# USBHUB-FE1_1S.net
KiCad netlist of a schematic drawn in Altium Designer
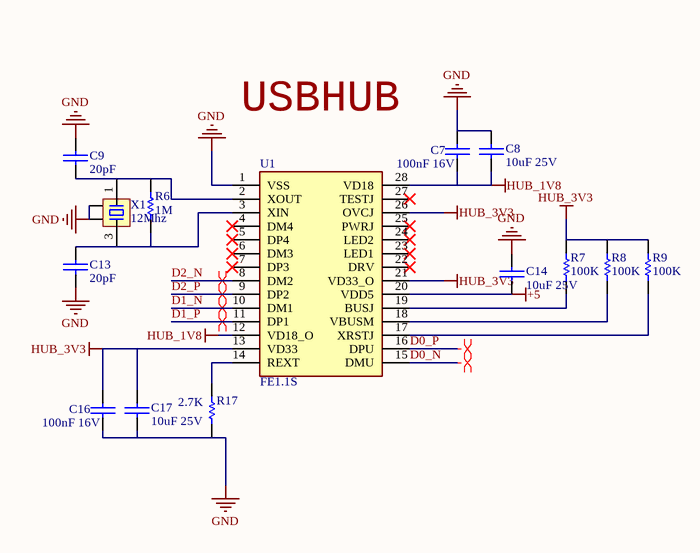
[diagram p0: USBHUB-FE1.1S.SchDoc]

(export (version "E")
  (design (tool "Eeschema 10.0.6"))
  (components
    (comp (ref "C7")
      (value "100nF 16V")
      (footprint "0402C")
      (description "CAP-NP")
      (libsource (lib "电容") (part "CAP-NP"))
    )
    (comp (ref "C8")
      (value "10uF 25V")
      (footprint "Capacitance:0805C")
      (description "CAP-NP")
      (libsource (lib "电容") (part "CAP-NP"))
    )
    (comp (ref "C9") (value "20pF") (footprint "0402C") (libsource (lib "电容") (part "CAP-NP")))
    (comp (ref "C13") (value "20pF") (footprint "0402C") (libsource (lib "电容") (part "CAP-NP")))
    (comp (ref "C14")
      (value "10uF 25V")
      (footprint "Capacitance:0805C")
      (description "CAP-NP")
      (libsource (lib "电容") (part "CAP-NP"))
    )
    (comp (ref "C16")
      (value "100nF 16V")
      (footprint "0402C")
      (description "CAP-NP")
      (libsource (lib "电容") (part "CAP-NP"))
    )
    (comp (ref "C17")
      (value "10uF 25V")
      (footprint "Capacitance:0805C")
      (description "CAP-NP")
      (libsource (lib "电容") (part "CAP-NP"))
    )
    (comp (ref "R6") (value "1M") (footprint "0402R") (libsource (lib "电阻") (part "RES")))
    (comp (ref "R7") (value "100K") (footprint "0402R") (libsource (lib "电阻") (part "RES")))
    (comp (ref "R8") (value "100K") (footprint "0402R") (libsource (lib "电阻") (part "RES")))
    (comp (ref "R9") (value "100K") (footprint "0402R") (libsource (lib "电阻") (part "RES")))
    (comp (ref "R17") (value "2.7K") (footprint "0402R") (libsource (lib "电阻") (part "RES")))
    (comp (ref "U1")
      (value "FE1.1S")
      (footprint "SamacSys:SOP64P600X175-28N")
      (description "Integrated Circuit")
      (libsource (lib "*") (part "FE1.1S"))
    )
    (comp (ref "X1")
      (value "12Mhz")
      (footprint "Crystals Oscillators:OSC 3225-4P")
      (description "XTAL-4P")
      (libsource (lib "晶振") (part "XTAL-4P"))
    )
  )
  (nets
    (net (code "1") (name "+5") (class "Default")
      (node (ref "C14") (pin "2") (pinfunction "2_2") (pintype "passive"))
      (node (ref "U1") (pin "20") (pinfunction "VDD5_20") (pintype "passive"))
    )
    (net (code "2") (name "/D0_N") (class "Default")
      (node (ref "U1") (pin "15") (pinfunction "DMU_15") (pintype "passive"))
    )
    (net (code "3") (name "/D0_P") (class "Default")
      (node (ref "U1") (pin "16") (pinfunction "DPU_16") (pintype "passive"))
    )
    (net (code "4") (name "/D1_N") (class "Default")
      (node (ref "U1") (pin "10") (pinfunction "DM1_10") (pintype "passive"))
    )
    (net (code "5") (name "/D1_P") (class "Default")
      (node (ref "U1") (pin "11") (pinfunction "DP1_11") (pintype "passive"))
    )
    (net (code "6") (name "/D2_N") (class "Default")
      (node (ref "U1") (pin "8") (pinfunction "DM2_8") (pintype "passive"))
    )
    (net (code "7") (name "/D2_P") (class "Default")
      (node (ref "U1") (pin "9") (pinfunction "DP2_9") (pintype "passive"))
    )
    (net (code "8") (name "GND") (class "Default")
      (node (ref "C13") (pin "1") (pinfunction "1_1") (pintype "passive"))
      (node (ref "C14") (pin "1") (pinfunction "1_1") (pintype "passive"))
      (node (ref "C16") (pin "1") (pinfunction "1_1") (pintype "passive"))
      (node (ref "C17") (pin "2") (pinfunction "2_2") (pintype "passive"))
      (node (ref "C7") (pin "2") (pinfunction "2_2") (pintype "passive"))
      (node (ref "C8") (pin "1") (pinfunction "1_1") (pintype "passive"))
      (node (ref "C9") (pin "2") (pinfunction "2_2") (pintype "passive"))
      (node (ref "R17") (pin "1") (pinfunction "1_1") (pintype "passive"))
      (node (ref "U1") (pin "1") (pinfunction "VSS_1") (pintype "passive"))
      (node (ref "X1") (pin "2") (pinfunction "2_2") (pintype "passive"))
      (node (ref "X1") (pin "4") (pinfunction "4_4") (pintype "passive"))
    )
    (net (code "9") (name "HUB_1V8") (class "Default")
      (node (ref "C7") (pin "1") (pinfunction "1_1") (pintype "passive"))
      (node (ref "C8") (pin "2") (pinfunction "2_2") (pintype "passive"))
      (node (ref "U1") (pin "12") (pinfunction "VD18_O_12") (pintype "passive"))
      (node (ref "U1") (pin "28") (pinfunction "VD18_28") (pintype "passive"))
    )
    (net (code "10") (name "HUB_3V3") (class "Default")
      (node (ref "C16") (pin "2") (pinfunction "2_2") (pintype "passive"))
      (node (ref "C17") (pin "1") (pinfunction "1_1") (pintype "passive"))
      (node (ref "R7") (pin "2") (pinfunction "2_2") (pintype "passive"))
      (node (ref "R8") (pin "2") (pinfunction "2_2") (pintype "passive"))
      (node (ref "R9") (pin "2") (pinfunction "2_2") (pintype "passive"))
      (node (ref "U1") (pin "13") (pinfunction "VD33_13") (pintype "passive"))
      (node (ref "U1") (pin "21") (pinfunction "VD33_O_21") (pintype "passive"))
      (node (ref "U1") (pin "26") (pinfunction "OVCJ_26") (pintype "passive"))
    )
    (net (code "11") (name "Net-(U1-BUSJ)") (class "Default")
      (node (ref "R7") (pin "1") (pinfunction "1_1") (pintype "passive"))
      (node (ref "U1") (pin "19") (pinfunction "BUSJ_19") (pintype "passive"))
    )
    (net (code "12") (name "Net-(U1-REXT)") (class "Default")
      (node (ref "R17") (pin "2") (pinfunction "2_2") (pintype "passive"))
      (node (ref "U1") (pin "14") (pinfunction "REXT_14") (pintype "passive"))
    )
    (net (code "13") (name "Net-(U1-VBUSM)") (class "Default")
      (node (ref "R8") (pin "1") (pinfunction "1_1") (pintype "passive"))
      (node (ref "U1") (pin "18") (pinfunction "VBUSM_18") (pintype "passive"))
    )
    (net (code "14") (name "Net-(U1-XIN)") (class "Default")
      (node (ref "C13") (pin "2") (pinfunction "2_2") (pintype "passive"))
      (node (ref "R6") (pin "1") (pinfunction "1_1") (pintype "passive"))
      (node (ref "U1") (pin "3") (pinfunction "XIN_3") (pintype "passive"))
      (node (ref "X1") (pin "3") (pinfunction "3_3") (pintype "passive"))
    )
    (net (code "15") (name "Net-(U1-XOUT)") (class "Default")
      (node (ref "C9") (pin "1") (pinfunction "1_1") (pintype "passive"))
      (node (ref "R6") (pin "2") (pinfunction "2_2") (pintype "passive"))
      (node (ref "U1") (pin "2") (pinfunction "XOUT_2") (pintype "passive"))
      (node (ref "X1") (pin "1") (pinfunction "1_1") (pintype "passive"))
    )
    (net (code "16") (name "Net-(U1-XRSTJ)") (class "Default")
      (node (ref "R9") (pin "1") (pinfunction "1_1") (pintype "passive"))
      (node (ref "U1") (pin "17") (pinfunction "XRSTJ_17") (pintype "passive"))
    )
    (net (code "17") (name "unconnected-(U1-DM3-Pad6)") (class "Default")
      (node (ref "U1") (pin "6") (pinfunction "DM3_6") (pintype "passive+no_connect"))
    )
    (net (code "18") (name "unconnected-(U1-DM4-Pad4)") (class "Default")
      (node (ref "U1") (pin "4") (pinfunction "DM4_4") (pintype "passive+no_connect"))
    )
    (net (code "19") (name "unconnected-(U1-DP3-Pad7)") (class "Default")
      (node (ref "U1") (pin "7") (pinfunction "DP3_7") (pintype "passive+no_connect"))
    )
    (net (code "20") (name "unconnected-(U1-DP4-Pad5)") (class "Default")
      (node (ref "U1") (pin "5") (pinfunction "DP4_5") (pintype "passive+no_connect"))
    )
    (net (code "21") (name "unconnected-(U1-DRV-Pad22)") (class "Default")
      (node (ref "U1") (pin "22") (pinfunction "DRV_22") (pintype "passive+no_connect"))
    )
    (net (code "22") (name "unconnected-(U1-LED1-Pad23)") (class "Default")
      (node (ref "U1") (pin "23") (pinfunction "LED1_23") (pintype "passive+no_connect"))
    )
    (net (code "23") (name "unconnected-(U1-LED2-Pad24)") (class "Default")
      (node (ref "U1") (pin "24") (pinfunction "LED2_24") (pintype "passive+no_connect"))
    )
    (net (code "24") (name "unconnected-(U1-PWRJ-Pad25)") (class "Default")
      (node (ref "U1") (pin "25") (pinfunction "PWRJ_25") (pintype "passive+no_connect"))
    )
    (net (code "25") (name "unconnected-(U1-TESTJ-Pad27)") (class "Default")
      (node (ref "U1") (pin "27") (pinfunction "TESTJ_27") (pintype "passive+no_connect"))
    )
  )
)
